# MCU.net
KiCad netlist of a schematic drawn in Altium Designer
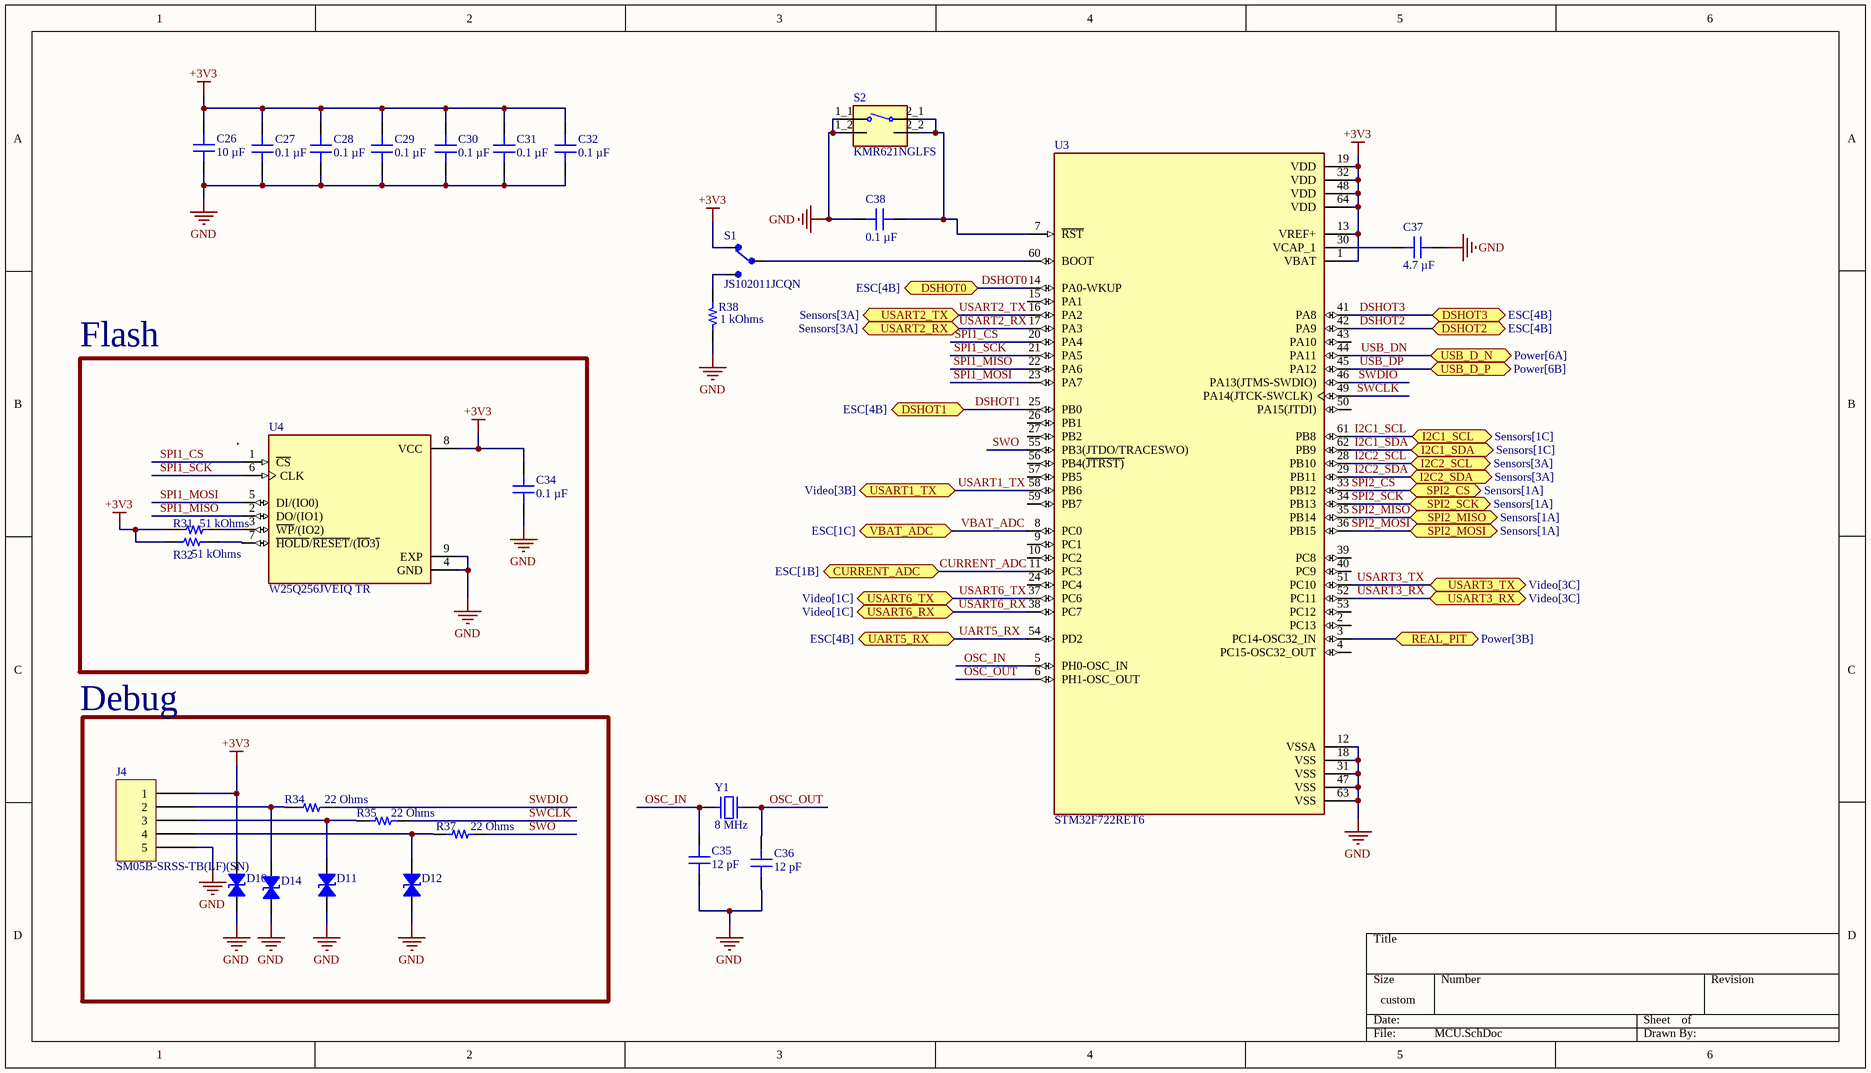
[diagram p0: MCU.SchDoc]

(export (version "E")
  (design (tool "Eeschema 10.0.6"))
  (components
    (comp (ref "C26")
      (value "10 µF")
      (footprint "CAP 0402_1005")
      (description "CAP CER 10UF 6.3V X5R 0402")
      (fields
        (field (name "PART NUMBER") "CL05A106MQ5NUNC")
        (field (name "CAPACITANCE") "10 µF")
        (field (name "MANUFACTURER") "Samsung Electro-Mechanics")
      )
      (libsource (lib "Celestial Altium Library - altium_library") (part "Capacitor"))
    )
    (comp (ref "C27")
      (value "0.1 µF")
      (footprint "CAP 0402_1005")
      (description "CAP CER 0.1UF 6.3V X5R 0402")
      (fields
        (field (name "PART NUMBER") "CC0402MRX5R5BB104")
        (field (name "CAPACITANCE") "0.1 µF")
        (field (name "MANUFACTURER") "Yageo")
      )
      (libsource (lib "Celestial Altium Library - altium_library") (part "Capacitor"))
    )
    (comp (ref "C28")
      (value "0.1 µF")
      (footprint "CAP 0402_1005")
      (description "CAP CER 0.1UF 6.3V X5R 0402")
      (fields
        (field (name "PART NUMBER") "CC0402MRX5R5BB104")
        (field (name "CAPACITANCE") "0.1 µF")
        (field (name "MANUFACTURER") "Yageo")
      )
      (libsource (lib "Celestial Altium Library - altium_library") (part "Capacitor"))
    )
    (comp (ref "C29")
      (value "0.1 µF")
      (footprint "CAP 0402_1005")
      (description "CAP CER 0.1UF 6.3V X5R 0402")
      (fields
        (field (name "PART NUMBER") "CC0402MRX5R5BB104")
        (field (name "CAPACITANCE") "0.1 µF")
        (field (name "MANUFACTURER") "Yageo")
      )
      (libsource (lib "Celestial Altium Library - altium_library") (part "Capacitor"))
    )
    (comp (ref "C30")
      (value "0.1 µF")
      (footprint "CAP 0402_1005")
      (description "CAP CER 0.1UF 6.3V X5R 0402")
      (fields
        (field (name "PART NUMBER") "CC0402MRX5R5BB104")
        (field (name "CAPACITANCE") "0.1 µF")
        (field (name "MANUFACTURER") "Yageo")
      )
      (libsource (lib "Celestial Altium Library - altium_library") (part "Capacitor"))
    )
    (comp (ref "C31")
      (value "0.1 µF")
      (footprint "CAP 0402_1005")
      (description "CAP CER 0.1UF 6.3V X5R 0402")
      (fields
        (field (name "PART NUMBER") "CC0402MRX5R5BB104")
        (field (name "CAPACITANCE") "0.1 µF")
        (field (name "MANUFACTURER") "Yageo")
      )
      (libsource (lib "Celestial Altium Library - altium_library") (part "Capacitor"))
    )
    (comp (ref "C32")
      (value "0.1 µF")
      (footprint "CAP 0402_1005")
      (description "CAP CER 0.1UF 6.3V X5R 0402")
      (fields
        (field (name "PART NUMBER") "CC0402MRX5R5BB104")
        (field (name "CAPACITANCE") "0.1 µF")
        (field (name "MANUFACTURER") "Yageo")
      )
      (libsource (lib "Celestial Altium Library - altium_library") (part "Capacitor"))
    )
    (comp (ref "C34")
      (value "0.1 µF")
      (footprint "CAP 0603_1608")
      (description "CAP CER 0.1UF 50V X7R 0603")
      (fields
        (field (name "PART NUMBER") "CL10B104KB8NNNC")
        (field (name "CAPACITANCE") "0.1 µF")
        (field (name "MANUFACTURER") "Samsung Electro-Mechanics")
      )
      (libsource (lib "Celestial Altium Library - altium_library") (part "Capacitor"))
    )
    (comp (ref "C35")
      (value "12 pF")
      (footprint "CAP 0402_1005")
      (description "CAP CER 12PF 10V NP0 0402")
      (fields
        (field (name "PART NUMBER") "C0402C120J8GAC7867")
        (field (name "CAPACITANCE") "12 pF")
        (field (name "MANUFACTURER") "KEMET")
      )
      (libsource (lib "Celestial Altium Library - altium_library") (part "Capacitor"))
    )
    (comp (ref "C36")
      (value "12 pF")
      (footprint "CAP 0402_1005")
      (description "CAP CER 12PF 10V NP0 0402")
      (fields
        (field (name "PART NUMBER") "C0402C120J8GAC7867")
        (field (name "CAPACITANCE") "12 pF")
        (field (name "MANUFACTURER") "KEMET")
      )
      (libsource (lib "Celestial Altium Library - altium_library") (part "Capacitor"))
    )
    (comp (ref "C37")
      (value "4.7 µF")
      (footprint "CAP 0402_1005")
      (description "CAP CER 4.7UF 6.3V X5R 0402")
      (fields
        (field (name "PART NUMBER") "C1005X5R0J475K050BC")
        (field (name "CAPACITANCE") "4.7 µF")
        (field (name "MANUFACTURER") "TDK Corporation")
      )
      (libsource (lib "Celestial Altium Library - altium_library") (part "Capacitor"))
    )
    (comp (ref "C38")
      (value "0.1 µF")
      (footprint "CAP 0402_1005")
      (description "CAP CER 0.1UF 6.3V X5R 0402")
      (fields
        (field (name "PART NUMBER") "CC0402MRX5R5BB104")
        (field (name "CAPACITANCE") "0.1 µF")
        (field (name "MANUFACTURER") "Yageo")
      )
      (libsource (lib "Celestial Altium Library - altium_library") (part "Capacitor"))
    )
    (comp (ref "D10")
      (value "DESD5V0U1BA-7")
      (footprint "SOD323")
      (description "TVS DIODE 5VWM 7.2VC SOD323")
      (fields (field (name "MANUFACTURER") "Diodes Incorporated"))
      (libsource (lib "Celestial Altium Library - altium_library") (part "Diode TVS"))
    )
    (comp (ref "D11")
      (value "DESD5V0U1BA-7")
      (footprint "SOD323")
      (description "TVS DIODE 5VWM 7.2VC SOD323")
      (fields (field (name "MANUFACTURER") "Diodes Incorporated"))
      (libsource (lib "Celestial Altium Library - altium_library") (part "Diode TVS"))
    )
    (comp (ref "D12")
      (value "DESD5V0U1BA-7")
      (footprint "SOD323")
      (description "TVS DIODE 5VWM 7.2VC SOD323")
      (fields (field (name "MANUFACTURER") "Diodes Incorporated"))
      (libsource (lib "Celestial Altium Library - altium_library") (part "Diode TVS"))
    )
    (comp (ref "D14")
      (value "DESD5V0U1BA-7")
      (footprint "SOD323")
      (description "TVS DIODE 5VWM 7.2VC SOD323")
      (fields (field (name "MANUFACTURER") "Diodes Incorporated"))
      (libsource (lib "Celestial Altium Library - altium_library") (part "Diode TVS"))
    )
    (comp (ref "J4")
      (value "SM05B-SRSS-TB(LF)(SN)")
      (footprint "JST SM05B-SRSS-TB")
      (description "CONN HEADER SMD R/A 5POS 1MM")
      (fields (field (name "MANUFACTURER") "JST Sales America Inc."))
      (libsource (lib "Celestial Altium Library - altium_library") (part "5 Pin"))
    )
    (comp (ref "R31")
      (value "51 kOhms")
      (footprint "RES 0603_1608")
      (description "RES SMD 51K OHM 1% 1/3W 0603")
      (fields (field (name "PART NUMBER") "CRCW060351K0FKEAHP") (field (name "MANUFACTURER") "Vishay Dale"))
      (libsource (lib "Celestial Altium Library - altium_library") (part "Resistor"))
    )
    (comp (ref "R32")
      (value "51 kOhms")
      (footprint "RES 0603_1608")
      (description "RES SMD 51K OHM 1% 1/3W 0603")
      (fields (field (name "PART NUMBER") "CRCW060351K0FKEAHP") (field (name "MANUFACTURER") "Vishay Dale"))
      (libsource (lib "Celestial Altium Library - altium_library") (part "Resistor"))
    )
    (comp (ref "R34")
      (value "22 Ohms")
      (footprint "YAGEO RES 0402_1005")
      (description "RES SMD 22 OHM 5% 1/16W 0402")
      (fields (field (name "PART NUMBER") "AC0402JR-0722RL") (field (name "MANUFACTURER") "Yageo"))
      (libsource (lib "Celestial Altium Library - altium_library") (part "Resistor"))
    )
    (comp (ref "R35")
      (value "22 Ohms")
      (footprint "YAGEO RES 0402_1005")
      (description "RES SMD 22 OHM 5% 1/16W 0402")
      (fields (field (name "PART NUMBER") "AC0402JR-0722RL") (field (name "MANUFACTURER") "Yageo"))
      (libsource (lib "Celestial Altium Library - altium_library") (part "Resistor"))
    )
    (comp (ref "R37")
      (value "22 Ohms")
      (footprint "YAGEO RES 0402_1005")
      (description "RES SMD 22 OHM 5% 1/16W 0402")
      (fields (field (name "PART NUMBER") "AC0402JR-0722RL") (field (name "MANUFACTURER") "Yageo"))
      (libsource (lib "Celestial Altium Library - altium_library") (part "Resistor"))
    )
    (comp (ref "R38")
      (value "1 kOhms")
      (footprint "YAGEO RES 0402_1005")
      (description "RES SMD 1K OHM 0.1% 1/16W 0402")
      (fields (field (name "PART NUMBER") "RT0402BRE071KL") (field (name "MANUFACTURER") "Yageo"))
      (libsource (lib "Celestial Altium Library - altium_library") (part "Resistor"))
    )
    (comp (ref "S1")
      (value "JS102011JCQN")
      (footprint "JS102011JCQN")
      (description "SWITCH SLIDE SPDT 300MA 6V")
      (fields (field (name "MANUFACTURER") "C&K"))
      (libsource (lib "PCB_Lib") (part "JS102011JCQN"))
    )
    (comp (ref "S2")
      (value "KMR621NGLFS")
      (footprint "KMR621NGLFS")
      (description "SWITCH TACTILE SPST-NO 0.05A 32V")
      (fields (field (name "MANUFACTURER") "C&K"))
      (libsource (lib "PCB_Lib") (part "KMR621NGLFS"))
    )
    (comp (ref "U3")
      (value "STM32F722RET6")
      (footprint "STM32F722RET6")
      (fields (field (name "MANUFACTURER") "STMicroelectronics"))
      (libsource (lib "PCB_Lib") (part "STM32F722RET6"))
    )
    (comp (ref "U4")
      (value "W25Q256JVEIQ TR")
      (footprint "W25Q256JVEIQ TR")
      (description "FLASH - NOR Memory IC 256Mbit SPI - Quad I/O 133 MHz 8-WSON (8x6)")
      (fields (field (name "MANUFACTURER") "Winbond Electronics"))
      (libsource (lib "PCB_Lib") (part "W25Q256JVEIQ TR"))
    )
    (comp (ref "Y1")
      (value "8 MHz")
      (footprint "NDK NX3225GD")
      (description "CRYSTAL 8.0000MHZ 8PF SMD")
      (fields
        (field (name "PART NUMBER") "NX3225GD-8MHZ-STD-CRA-3")
        (field (name "MANUFACTURER") "NDK America, Inc.")
      )
      (libsource (lib "Celestial Altium Library - altium_library") (part "NDK NX3225GD"))
    )
  )
  (nets
    (net (code "1") (name "+3V3") (class "Default")
      (node (ref "C26") (pin "2") (pinfunction "2_2") (pintype "passive"))
      (node (ref "C27") (pin "2") (pinfunction "2_2") (pintype "passive"))
      (node (ref "C28") (pin "2") (pinfunction "2_2") (pintype "passive"))
      (node (ref "C29") (pin "2") (pinfunction "2_2") (pintype "passive"))
      (node (ref "C30") (pin "2") (pinfunction "2_2") (pintype "passive"))
      (node (ref "C31") (pin "2") (pinfunction "2_2") (pintype "passive"))
      (node (ref "C32") (pin "2") (pinfunction "2_2") (pintype "passive"))
      (node (ref "C34") (pin "2") (pinfunction "2_2") (pintype "passive"))
      (node (ref "D10") (pin "2") (pinfunction "2_2") (pintype "passive"))
      (node (ref "J4") (pin "1") (pinfunction "1_1") (pintype "passive"))
      (node (ref "R31") (pin "2") (pinfunction "2_2") (pintype "passive"))
      (node (ref "R32") (pin "2") (pinfunction "2_2") (pintype "passive"))
      (node (ref "S1") (pin "1") (pinfunction "1_1") (pintype "passive"))
      (node (ref "U3") (pin "1") (pinfunction "VBAT_1") (pintype "power_in"))
      (node (ref "U3") (pin "13") (pinfunction "VREF+_13") (pintype "power_in"))
      (node (ref "U3") (pin "19") (pinfunction "VDD_19") (pintype "power_in"))
      (node (ref "U3") (pin "32") (pinfunction "VDD_32") (pintype "power_in"))
      (node (ref "U3") (pin "48") (pinfunction "VDD_48") (pintype "power_in"))
      (node (ref "U3") (pin "64") (pinfunction "VDD_64") (pintype "power_in"))
      (node (ref "U4") (pin "8") (pinfunction "VCC_8") (pintype "power_in"))
    )
    (net (code "2") (name "/CURRENT_ADC") (class "Default")
      (node (ref "U3") (pin "11") (pinfunction "PC3_11") (pintype "bidirectional"))
    )
    (net (code "3") (name "/DSHOT0") (class "Default")
      (node (ref "U3") (pin "14") (pinfunction "PA0-WKUP_14") (pintype "bidirectional"))
    )
    (net (code "4") (name "/DSHOT1") (class "Default")
      (node (ref "U3") (pin "25") (pinfunction "PB0_25") (pintype "bidirectional"))
    )
    (net (code "5") (name "/DSHOT2") (class "Default")
      (node (ref "U3") (pin "42") (pinfunction "PA9_42") (pintype "bidirectional"))
    )
    (net (code "6") (name "/DSHOT3") (class "Default")
      (node (ref "U3") (pin "41") (pinfunction "PA8_41") (pintype "bidirectional"))
    )
    (net (code "7") (name "/I2C1_SCL") (class "Default")
      (node (ref "U3") (pin "61") (pinfunction "PB8_61") (pintype "bidirectional"))
    )
    (net (code "8") (name "/I2C1_SDA") (class "Default")
      (node (ref "U3") (pin "62") (pinfunction "PB9_62") (pintype "bidirectional"))
    )
    (net (code "9") (name "/I2C2_SCL") (class "Default")
      (node (ref "U3") (pin "28") (pinfunction "PB10_28") (pintype "bidirectional"))
    )
    (net (code "10") (name "/I2C2_SDA") (class "Default")
      (node (ref "U3") (pin "29") (pinfunction "PB11_29") (pintype "bidirectional"))
    )
    (net (code "11") (name "/OSC_IN") (class "Default")
      (node (ref "C35") (pin "2") (pinfunction "2_2") (pintype "passive"))
      (node (ref "U3") (pin "5") (pinfunction "PH0-OSC_IN_5") (pintype "bidirectional"))
      (node (ref "Y1") (pin "1") (pinfunction "1_1") (pintype "passive"))
    )
    (net (code "12") (name "/OSC_OUT") (class "Default")
      (node (ref "C36") (pin "2") (pinfunction "2_2") (pintype "passive"))
      (node (ref "U3") (pin "6") (pinfunction "PH1-OSC_OUT_6") (pintype "bidirectional"))
      (node (ref "Y1") (pin "2") (pinfunction "2_2") (pintype "passive"))
    )
    (net (code "13") (name "/REAL_PIT") (class "Default")
      (node (ref "U3") (pin "3") (pinfunction "PC14-OSC32_IN_3") (pintype "bidirectional"))
    )
    (net (code "14") (name "/SPI1_CS") (class "Default")
      (node (ref "U3") (pin "20") (pinfunction "PA4_20") (pintype "bidirectional"))
      (node (ref "U4") (pin "1") (pinfunction "~{CS}_1") (pintype "input"))
    )
    (net (code "15") (name "/SPI1_MISO") (class "Default")
      (node (ref "U3") (pin "22") (pinfunction "PA6_22") (pintype "bidirectional"))
      (node (ref "U4") (pin "2") (pinfunction "DO/(IO1)_2") (pintype "bidirectional"))
    )
    (net (code "16") (name "/SPI1_MOSI") (class "Default")
      (node (ref "U3") (pin "23") (pinfunction "PA7_23") (pintype "bidirectional"))
      (node (ref "U4") (pin "5") (pinfunction "DI/(IO0)_5") (pintype "bidirectional"))
    )
    (net (code "17") (name "/SPI1_SCK") (class "Default")
      (node (ref "U3") (pin "21") (pinfunction "PA5_21") (pintype "bidirectional"))
      (node (ref "U4") (pin "6") (pinfunction "CLK_6") (pintype "input"))
    )
    (net (code "18") (name "/SPI2_CS") (class "Default")
      (node (ref "U3") (pin "33") (pinfunction "PB12_33") (pintype "bidirectional"))
    )
    (net (code "19") (name "/SPI2_MISO") (class "Default")
      (node (ref "U3") (pin "35") (pinfunction "PB14_35") (pintype "bidirectional"))
    )
    (net (code "20") (name "/SPI2_MOSI") (class "Default")
      (node (ref "U3") (pin "36") (pinfunction "PB15_36") (pintype "bidirectional"))
    )
    (net (code "21") (name "/SPI2_SCK") (class "Default")
      (node (ref "U3") (pin "34") (pinfunction "PB13_34") (pintype "bidirectional"))
    )
    (net (code "22") (name "/SWCLK") (class "Default")
      (node (ref "R35") (pin "2") (pinfunction "2_2") (pintype "passive"))
      (node (ref "U3") (pin "49") (pinfunction "PA14(JTCK-SWCLK)_49") (pintype "bidirectional"))
    )
    (net (code "23") (name "/SWDIO") (class "Default")
      (node (ref "R34") (pin "2") (pinfunction "2_2") (pintype "passive"))
      (node (ref "U3") (pin "46") (pinfunction "PA13(JTMS-SWDIO)_46") (pintype "bidirectional"))
    )
    (net (code "24") (name "/SWO") (class "Default")
      (node (ref "R37") (pin "2") (pinfunction "2_2") (pintype "passive"))
      (node (ref "U3") (pin "55") (pinfunction "PB3(JTDO/TRACESWO)_55") (pintype "bidirectional"))
    )
    (net (code "25") (name "/UART5_RX") (class "Default")
      (node (ref "U3") (pin "54") (pinfunction "PD2_54") (pintype "bidirectional"))
    )
    (net (code "26") (name "/USART1_TX") (class "Default")
      (node (ref "U3") (pin "58") (pinfunction "PB6_58") (pintype "bidirectional"))
    )
    (net (code "27") (name "/USART2_RX") (class "Default")
      (node (ref "U3") (pin "17") (pinfunction "PA3_17") (pintype "bidirectional"))
    )
    (net (code "28") (name "/USART2_TX") (class "Default")
      (node (ref "U3") (pin "16") (pinfunction "PA2_16") (pintype "bidirectional"))
    )
    (net (code "29") (name "/USART3_RX") (class "Default")
      (node (ref "U3") (pin "52") (pinfunction "PC11_52") (pintype "bidirectional"))
    )
    (net (code "30") (name "/USART3_TX") (class "Default")
      (node (ref "U3") (pin "51") (pinfunction "PC10_51") (pintype "bidirectional"))
    )
    (net (code "31") (name "/USART6_RX") (class "Default")
      (node (ref "U3") (pin "38") (pinfunction "PC7_38") (pintype "bidirectional"))
    )
    (net (code "32") (name "/USART6_TX") (class "Default")
      (node (ref "U3") (pin "37") (pinfunction "PC6_37") (pintype "bidirectional"))
    )
    (net (code "33") (name "/USB_DN") (class "Default")
      (node (ref "U3") (pin "44") (pinfunction "PA11_44") (pintype "bidirectional"))
    )
    (net (code "34") (name "/USB_DP") (class "Default")
      (node (ref "U3") (pin "45") (pinfunction "PA12_45") (pintype "bidirectional"))
    )
    (net (code "35") (name "/VBAT_ADC") (class "Default")
      (node (ref "U3") (pin "8") (pinfunction "PC0_8") (pintype "bidirectional"))
    )
    (net (code "36") (name "GND") (class "Default")
      (node (ref "C26") (pin "1") (pinfunction "1_1") (pintype "passive"))
      (node (ref "C27") (pin "1") (pinfunction "1_1") (pintype "passive"))
      (node (ref "C28") (pin "1") (pinfunction "1_1") (pintype "passive"))
      (node (ref "C29") (pin "1") (pinfunction "1_1") (pintype "passive"))
      (node (ref "C30") (pin "1") (pinfunction "1_1") (pintype "passive"))
      (node (ref "C31") (pin "1") (pinfunction "1_1") (pintype "passive"))
      (node (ref "C32") (pin "1") (pinfunction "1_1") (pintype "passive"))
      (node (ref "C34") (pin "1") (pinfunction "1_1") (pintype "passive"))
      (node (ref "C35") (pin "1") (pinfunction "1_1") (pintype "passive"))
      (node (ref "C36") (pin "1") (pinfunction "1_1") (pintype "passive"))
      (node (ref "C37") (pin "2") (pinfunction "2_2") (pintype "passive"))
      (node (ref "C38") (pin "1") (pinfunction "1_1") (pintype "passive"))
      (node (ref "D10") (pin "1") (pinfunction "1_1") (pintype "passive"))
      (node (ref "D11") (pin "1") (pinfunction "1_1") (pintype "passive"))
      (node (ref "D12") (pin "1") (pinfunction "1_1") (pintype "passive"))
      (node (ref "D14") (pin "1") (pinfunction "1_1") (pintype "passive"))
      (node (ref "J4") (pin "5") (pinfunction "5_5") (pintype "passive"))
      (node (ref "R38") (pin "2") (pinfunction "2_2") (pintype "passive"))
      (node (ref "S2") (pin "1_1") (pinfunction "1_1_1") (pintype "passive"))
      (node (ref "S2") (pin "1_2") (pinfunction "1_1_2") (pintype "passive"))
      (node (ref "U3") (pin "12") (pinfunction "VSSA_12") (pintype "power_in"))
      (node (ref "U3") (pin "18") (pinfunction "VSS_18") (pintype "power_in"))
      (node (ref "U3") (pin "31") (pinfunction "VSS_31") (pintype "power_in"))
      (node (ref "U3") (pin "47") (pinfunction "VSS_47") (pintype "power_in"))
      (node (ref "U3") (pin "63") (pinfunction "VSS_63") (pintype "power_in"))
      (node (ref "U4") (pin "4") (pinfunction "GND_4") (pintype "power_in"))
      (node (ref "U4") (pin "9") (pinfunction "EXP_9") (pintype "passive"))
    )
    (net (code "37") (name "Net-(D11-Pad2)") (class "Default")
      (node (ref "D11") (pin "2") (pinfunction "2_2") (pintype "passive"))
      (node (ref "J4") (pin "3") (pinfunction "3_3") (pintype "passive"))
      (node (ref "R35") (pin "1") (pinfunction "1_1") (pintype "passive"))
    )
    (net (code "38") (name "Net-(D12-Pad2)") (class "Default")
      (node (ref "D12") (pin "2") (pinfunction "2_2") (pintype "passive"))
      (node (ref "J4") (pin "4") (pinfunction "4_4") (pintype "passive"))
      (node (ref "R37") (pin "1") (pinfunction "1_1") (pintype "passive"))
    )
    (net (code "39") (name "Net-(D14-Pad2)") (class "Default")
      (node (ref "D14") (pin "2") (pinfunction "2_2") (pintype "passive"))
      (node (ref "J4") (pin "2") (pinfunction "2_2") (pintype "passive"))
      (node (ref "R34") (pin "1") (pinfunction "1_1") (pintype "passive"))
    )
    (net (code "40") (name "Net-(R38-Pad1)") (class "Default")
      (node (ref "R38") (pin "1") (pinfunction "1_1") (pintype "passive"))
      (node (ref "S1") (pin "3") (pinfunction "3_3") (pintype "passive"))
    )
    (net (code "41") (name "Net-(U3-BOOT)") (class "Default")
      (node (ref "S1") (pin "2") (pinfunction "2_2") (pintype "passive"))
      (node (ref "U3") (pin "60") (pinfunction "BOOT_60") (pintype "bidirectional"))
    )
    (net (code "42") (name "Net-(U3-VCAP_1)") (class "Default")
      (node (ref "C37") (pin "1") (pinfunction "1_1") (pintype "passive"))
      (node (ref "U3") (pin "30") (pinfunction "VCAP_1_30") (pintype "power_in"))
    )
    (net (code "43") (name "Net-(U3-~{RST})") (class "Default")
      (node (ref "C38") (pin "2") (pinfunction "2_2") (pintype "passive"))
      (node (ref "S2") (pin "2_1") (pinfunction "2_2_1") (pintype "passive"))
      (node (ref "S2") (pin "2_2") (pinfunction "2_2_2") (pintype "passive"))
      (node (ref "U3") (pin "7") (pinfunction "~{RST}_7") (pintype "input"))
    )
    (net (code "44") (name "Net-(U4-~{HOLD}{slash}~{RESET}{slash}(~{IO}3~{)})") (class "Default")
      (node (ref "R32") (pin "1") (pinfunction "1_1") (pintype "passive"))
      (node (ref "U4") (pin "7") (pinfunction "~{HOLD}/~{RESET}/(~{IO}3~{)}_7") (pintype "bidirectional"))
    )
    (net (code "45") (name "Net-(U4-~{WP}{slash}(IO2))") (class "Default")
      (node (ref "R31") (pin "1") (pinfunction "1_1") (pintype "passive"))
      (node (ref "U4") (pin "3") (pinfunction "~{WP}/(IO2)_3") (pintype "bidirectional"))
    )
    (net (code "46") (name "unconnected-(U3-PA1-Pad15)") (class "Default")
      (node (ref "U3") (pin "15") (pinfunction "PA1_15") (pintype "bidirectional"))
    )
    (net (code "47") (name "unconnected-(U3-PA10-Pad43)") (class "Default")
      (node (ref "U3") (pin "43") (pinfunction "PA10_43") (pintype "bidirectional"))
    )
    (net (code "48") (name "unconnected-(U3-PA15(JTDI)-Pad50)") (class "Default")
      (node (ref "U3") (pin "50") (pinfunction "PA15(JTDI)_50") (pintype "bidirectional"))
    )
    (net (code "49") (name "unconnected-(U3-PB1-Pad26)") (class "Default")
      (node (ref "U3") (pin "26") (pinfunction "PB1_26") (pintype "bidirectional"))
    )
    (net (code "50") (name "unconnected-(U3-PB2-Pad27)") (class "Default")
      (node (ref "U3") (pin "27") (pinfunction "PB2_27") (pintype "bidirectional"))
    )
    (net (code "51") (name "unconnected-(U3-PB4(~{JTRST)}-Pad56)") (class "Default")
      (node (ref "U3") (pin "56") (pinfunction "PB4(~{JTRST)}_56") (pintype "bidirectional"))
    )
    (net (code "52") (name "unconnected-(U3-PB5-Pad57)") (class "Default")
      (node (ref "U3") (pin "57") (pinfunction "PB5_57") (pintype "bidirectional"))
    )
    (net (code "53") (name "unconnected-(U3-PB7-Pad59)") (class "Default")
      (node (ref "U3") (pin "59") (pinfunction "PB7_59") (pintype "bidirectional"))
    )
    (net (code "54") (name "unconnected-(U3-PC1-Pad9)") (class "Default")
      (node (ref "U3") (pin "9") (pinfunction "PC1_9") (pintype "bidirectional"))
    )
    (net (code "55") (name "unconnected-(U3-PC2-Pad10)") (class "Default")
      (node (ref "U3") (pin "10") (pinfunction "PC2_10") (pintype "bidirectional"))
    )
    (net (code "56") (name "unconnected-(U3-PC4-Pad24)") (class "Default")
      (node (ref "U3") (pin "24") (pinfunction "PC4_24") (pintype "bidirectional"))
    )
    (net (code "57") (name "unconnected-(U3-PC8-Pad39)") (class "Default")
      (node (ref "U3") (pin "39") (pinfunction "PC8_39") (pintype "bidirectional"))
    )
    (net (code "58") (name "unconnected-(U3-PC9-Pad40)") (class "Default")
      (node (ref "U3") (pin "40") (pinfunction "PC9_40") (pintype "bidirectional"))
    )
    (net (code "59") (name "unconnected-(U3-PC12-Pad53)") (class "Default")
      (node (ref "U3") (pin "53") (pinfunction "PC12_53") (pintype "bidirectional"))
    )
    (net (code "60") (name "unconnected-(U3-PC13-Pad2)") (class "Default")
      (node (ref "U3") (pin "2") (pinfunction "PC13_2") (pintype "bidirectional"))
    )
    (net (code "61") (name "unconnected-(U3-PC15-OSC32_OUT-Pad4)") (class "Default")
      (node (ref "U3") (pin "4") (pinfunction "PC15-OSC32_OUT_4") (pintype "bidirectional"))
    )
  )
)
